# buck_converter.net
KiCad netlist of a schematic drawn in Altium Designer
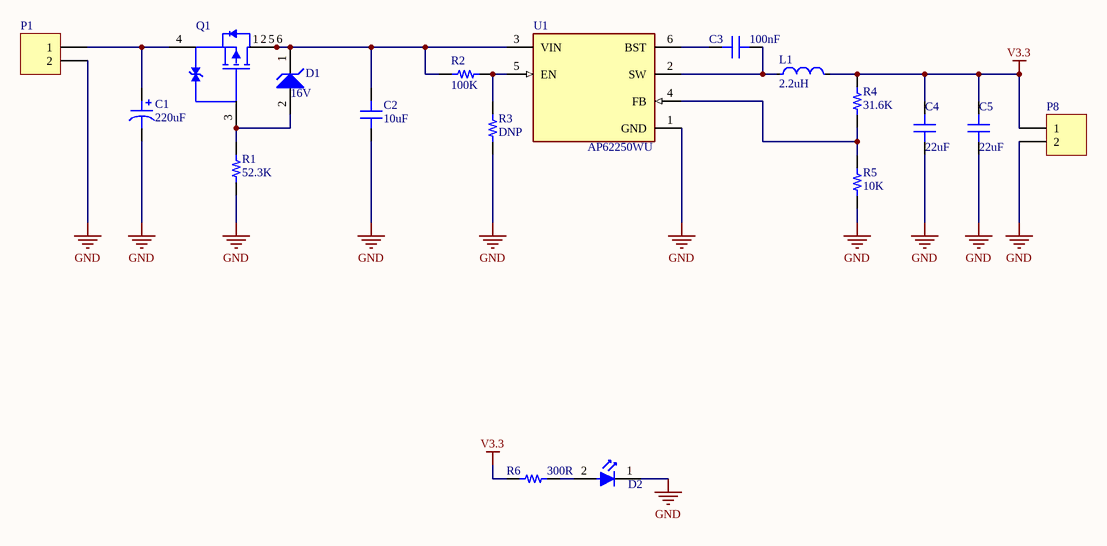
[diagram p0: buck_converter.SchDoc]

(export (version "E")
  (design (tool "Eeschema 10.0.6"))
  (components
    (comp (ref "C1")
      (value "220uF")
      (footprint "CAP TH ALUM ELEC D10.00mm S5.00mm H12.50mm")
      (description "SMT Polarised Capacitor")
      (fields (field (name "MF") "KEMET") (field (name "MP") "ESK227M035AH1AA"))
      (libsource (lib "Capacitor") (part "Polarised Capacitor"))
    )
    (comp (ref "C2")
      (value "10uF")
      (footprint "CAP 0603_1608")
      (description "SMT Capacitor")
      (fields (field (name "MF") "Murata") (field (name "MP") "GRM188R61C106MAALD"))
      (libsource (lib "Capacitor") (part "Capacitor"))
    )
    (comp (ref "C3")
      (value "100nF")
      (footprint "CAP 0603_1608")
      (description "SMT Capacitor")
      (fields (field (name "MF") "TDK") (field (name "MP") "CGA3E2X7R1E104K080AA"))
      (libsource (lib "Capacitor") (part "Capacitor"))
    )
    (comp (ref "C4")
      (value "22uF")
      (footprint "CAP 0603_1608")
      (description "SMT Capacitor")
      (fields (field (name "MF") "Murata") (field (name "MP") "GRM188R61A226ME15D"))
      (libsource (lib "Capacitor") (part "Capacitor"))
    )
    (comp (ref "C5")
      (value "22uF")
      (footprint "CAP 0603_1608")
      (description "SMT Capacitor")
      (fields (field (name "MF") "Murata") (field (name "MP") "GRM188R61A226ME15D"))
      (libsource (lib "Capacitor") (part "Capacitor"))
    )
    (comp (ref "D1")
      (value "16V")
      (footprint "Diodes_SOD-123_0")
      (description "Zener Voltage Regulator")
      (fields (field (name "MANUFACTURER") "On Semiconductor") (field (name "MF") "Onsemi"))
      (libsource (lib "Diode") (part "Zener Diode"))
    )
    (comp (ref "D2")
      (value "Red")
      (footprint "Würth_Elektronik_0_MFG")
      (description "Led Diffused SMD")
      (fields (field (name "MF") "LiteOn") (field (name "MP") "LTST-C190KRKT"))
      (libsource (lib "Diode") (part "LED SMD"))
    )
    (comp (ref "L1")
      (value "2.2uH")
      (footprint "Vishay_IHLP-2020CZ-FP_1_905x2_79-3D_3_0_MFG")
      (description "Fixed Inductors 2.2uH 20% High Temp AEC-Q200")
      (fields (field (name "MF") "Vishay") (field (name "MP") "IHLP2020CZER2R2M11"))
      (libsource (lib "Inductor") (part "Inductor_sm"))
    )
    (comp (ref "P1")
      (value "*")
      (footprint "TEConn_EP2.5_1x2")
      (description "Header, 2-Pin, Right Angle")
      (fields
        (field (name "MF") "TE Connectivity")
        (field (name "MP") "1744426-2")
        (field (name "PUBLISHER") "Altium Limited")
      )
      (libsource (lib "Connector") (part "Header 2H"))
    )
    (comp (ref "P8")
      (value "DNP")
      (footprint "HDR1X2")
      (description "Header, 2-Pin")
      (fields (field (name "PUBLISHER") "Altium Limited"))
      (libsource (lib "Connector") (part "Header 2"))
    )
    (comp (ref "Q1")
      (value "P Mosfet")
      (footprint "Diodes_Inc._TSOT26_MFG")
      (description "P-Channel Enhancement Mode MOS Transistor, 3-Pin SOT23")
      (fields (field (name "MF") "Vishay") (field (name "MP") "SI3421DV-T1-GE3"))
      (libsource (lib "Mosfet") (part "Mosfet-P-6_ESD"))
    )
    (comp (ref "R1")
      (value "52.3K")
      (footprint "RES 0603_1608")
      (description "SMT Resistor")
      (fields (field (name "MF") "YAGEO") (field (name "MP") "AC0603FR-0752K3L"))
      (libsource (lib "Resistor") (part "Resistor"))
    )
    (comp (ref "R2")
      (value "100K")
      (footprint "RES 0603_1608")
      (description "SMT Resistor")
      (fields (field (name "MF") "YAGEO") (field (name "MP") "AC0603FR-07100KL"))
      (libsource (lib "Resistor") (part "Resistor"))
    )
    (comp (ref "R3")
      (value "DNP")
      (footprint "RES 0603_1608")
      (description "SMT Resistor")
      (fields (field (name "MF") "YAGEO") (field (name "MP") "AC0603FR-07100KL"))
      (libsource (lib "Resistor") (part "Resistor"))
    )
    (comp (ref "R4")
      (value "31.6K")
      (footprint "RES 0603_1608")
      (description "SMT Resistor")
      (fields (field (name "MF") "YAGEO") (field (name "MP") "AC0603FR-0731K6L"))
      (libsource (lib "Resistor") (part "Resistor"))
    )
    (comp (ref "R5")
      (value "10K")
      (footprint "RES 0603_1608")
      (description "SMT Resistor")
      (fields (field (name "MF") "YAGEO") (field (name "MP") "AC0603FR-0710KL"))
      (libsource (lib "Resistor") (part "Resistor"))
    )
    (comp (ref "R6")
      (value "300R")
      (footprint "RES 0603_1608")
      (description "SMT Resistor")
      (fields (field (name "MF") "YAGEO") (field (name "MP") "AC0603FR-07300RL"))
      (libsource (lib "Resistor") (part "Resistor"))
    )
    (comp (ref "U1")
      (value "AP62250WU")
      (footprint "Diodes_Inc._TSOT26_MFG")
      (description "Switching Voltage Regulators DCDC Conv HV Buck TSOT26")
      (fields (field (name "MF") "Diodes Incorporated") (field (name "MP") "AP62250WU-7"))
      (libsource (lib "SwitchingRegulators") (part "AP62250WU"))
    )
  )
  (nets
    (net (code "1") (name "GND") (class "Default")
      (node (ref "C1") (pin "2") (pinfunction "2_2") (pintype "passive"))
      (node (ref "C2") (pin "2") (pinfunction "2_2") (pintype "passive"))
      (node (ref "C4") (pin "2") (pinfunction "2_2") (pintype "passive"))
      (node (ref "C5") (pin "2") (pinfunction "2_2") (pintype "passive"))
      (node (ref "D2") (pin "1") (pinfunction "C_1") (pintype "passive"))
      (node (ref "P1") (pin "2") (pinfunction "2_2") (pintype "passive"))
      (node (ref "P8") (pin "2") (pinfunction "2_2") (pintype "passive"))
      (node (ref "R1") (pin "2") (pinfunction "2_2") (pintype "passive"))
      (node (ref "R3") (pin "2") (pinfunction "2_2") (pintype "passive"))
      (node (ref "R5") (pin "2") (pinfunction "2_2") (pintype "passive"))
      (node (ref "U1") (pin "1") (pinfunction "GND_1") (pintype "power_in"))
    )
    (net (code "2") (name "Net-(D1-A)") (class "Default")
      (node (ref "D1") (pin "2") (pinfunction "A_2") (pintype "passive"))
      (node (ref "Q1") (pin "3") (pinfunction "G_3") (pintype "passive"))
      (node (ref "R1") (pin "1") (pinfunction "1_1") (pintype "passive"))
    )
    (net (code "3") (name "Net-(D1-K)") (class "Default")
      (node (ref "C2") (pin "1") (pinfunction "1_1") (pintype "passive"))
      (node (ref "D1") (pin "1") (pinfunction "K_1") (pintype "passive"))
      (node (ref "Q1") (pin "1") (pinfunction "D_1") (pintype "passive"))
      (node (ref "Q1") (pin "2") (pinfunction "D_2") (pintype "passive"))
      (node (ref "Q1") (pin "5") (pinfunction "D_5") (pintype "passive"))
      (node (ref "Q1") (pin "6") (pinfunction "D_6") (pintype "passive"))
      (node (ref "R2") (pin "2") (pinfunction "2_2") (pintype "passive"))
      (node (ref "U1") (pin "3") (pinfunction "VIN_3") (pintype "power_in"))
    )
    (net (code "4") (name "Net-(D2-A)") (class "Default")
      (node (ref "D2") (pin "2") (pinfunction "A_2") (pintype "passive"))
      (node (ref "R6") (pin "2") (pinfunction "2_2") (pintype "passive"))
    )
    (net (code "5") (name "Net-(Q1-S)") (class "Default")
      (node (ref "C1") (pin "1") (pinfunction "1_1") (pintype "passive"))
      (node (ref "P1") (pin "1") (pinfunction "1_1") (pintype "passive"))
      (node (ref "Q1") (pin "4") (pinfunction "S_4") (pintype "passive"))
    )
    (net (code "6") (name "Net-(U1-BST)") (class "Default")
      (node (ref "C3") (pin "1") (pinfunction "1_1") (pintype "passive"))
      (node (ref "U1") (pin "6") (pinfunction "BST_6") (pintype "passive"))
    )
    (net (code "7") (name "Net-(U1-EN)") (class "Default")
      (node (ref "R2") (pin "1") (pinfunction "1_1") (pintype "passive"))
      (node (ref "R3") (pin "1") (pinfunction "1_1") (pintype "passive"))
      (node (ref "U1") (pin "5") (pinfunction "EN_5") (pintype "input"))
    )
    (net (code "8") (name "Net-(U1-FB)") (class "Default")
      (node (ref "R4") (pin "2") (pinfunction "2_2") (pintype "passive"))
      (node (ref "R5") (pin "1") (pinfunction "1_1") (pintype "passive"))
      (node (ref "U1") (pin "4") (pinfunction "FB_4") (pintype "input"))
    )
    (net (code "9") (name "Net-(U1-SW)") (class "Default")
      (node (ref "C3") (pin "2") (pinfunction "2_2") (pintype "passive"))
      (node (ref "L1") (pin "1") (pinfunction "1_1") (pintype "passive"))
      (node (ref "U1") (pin "2") (pinfunction "SW_2") (pintype "passive"))
    )
    (net (code "10") (name "V3.3") (class "Default")
      (node (ref "C4") (pin "1") (pinfunction "1_1") (pintype "passive"))
      (node (ref "C5") (pin "1") (pinfunction "1_1") (pintype "passive"))
      (node (ref "L1") (pin "2") (pinfunction "2_2") (pintype "passive"))
      (node (ref "P8") (pin "1") (pinfunction "1_1") (pintype "passive"))
      (node (ref "R4") (pin "1") (pinfunction "1_1") (pintype "passive"))
      (node (ref "R6") (pin "1") (pinfunction "1_1") (pintype "passive"))
    )
  )
)
